# mother.net
KiCad netlist of a schematic drawn in EAGLE
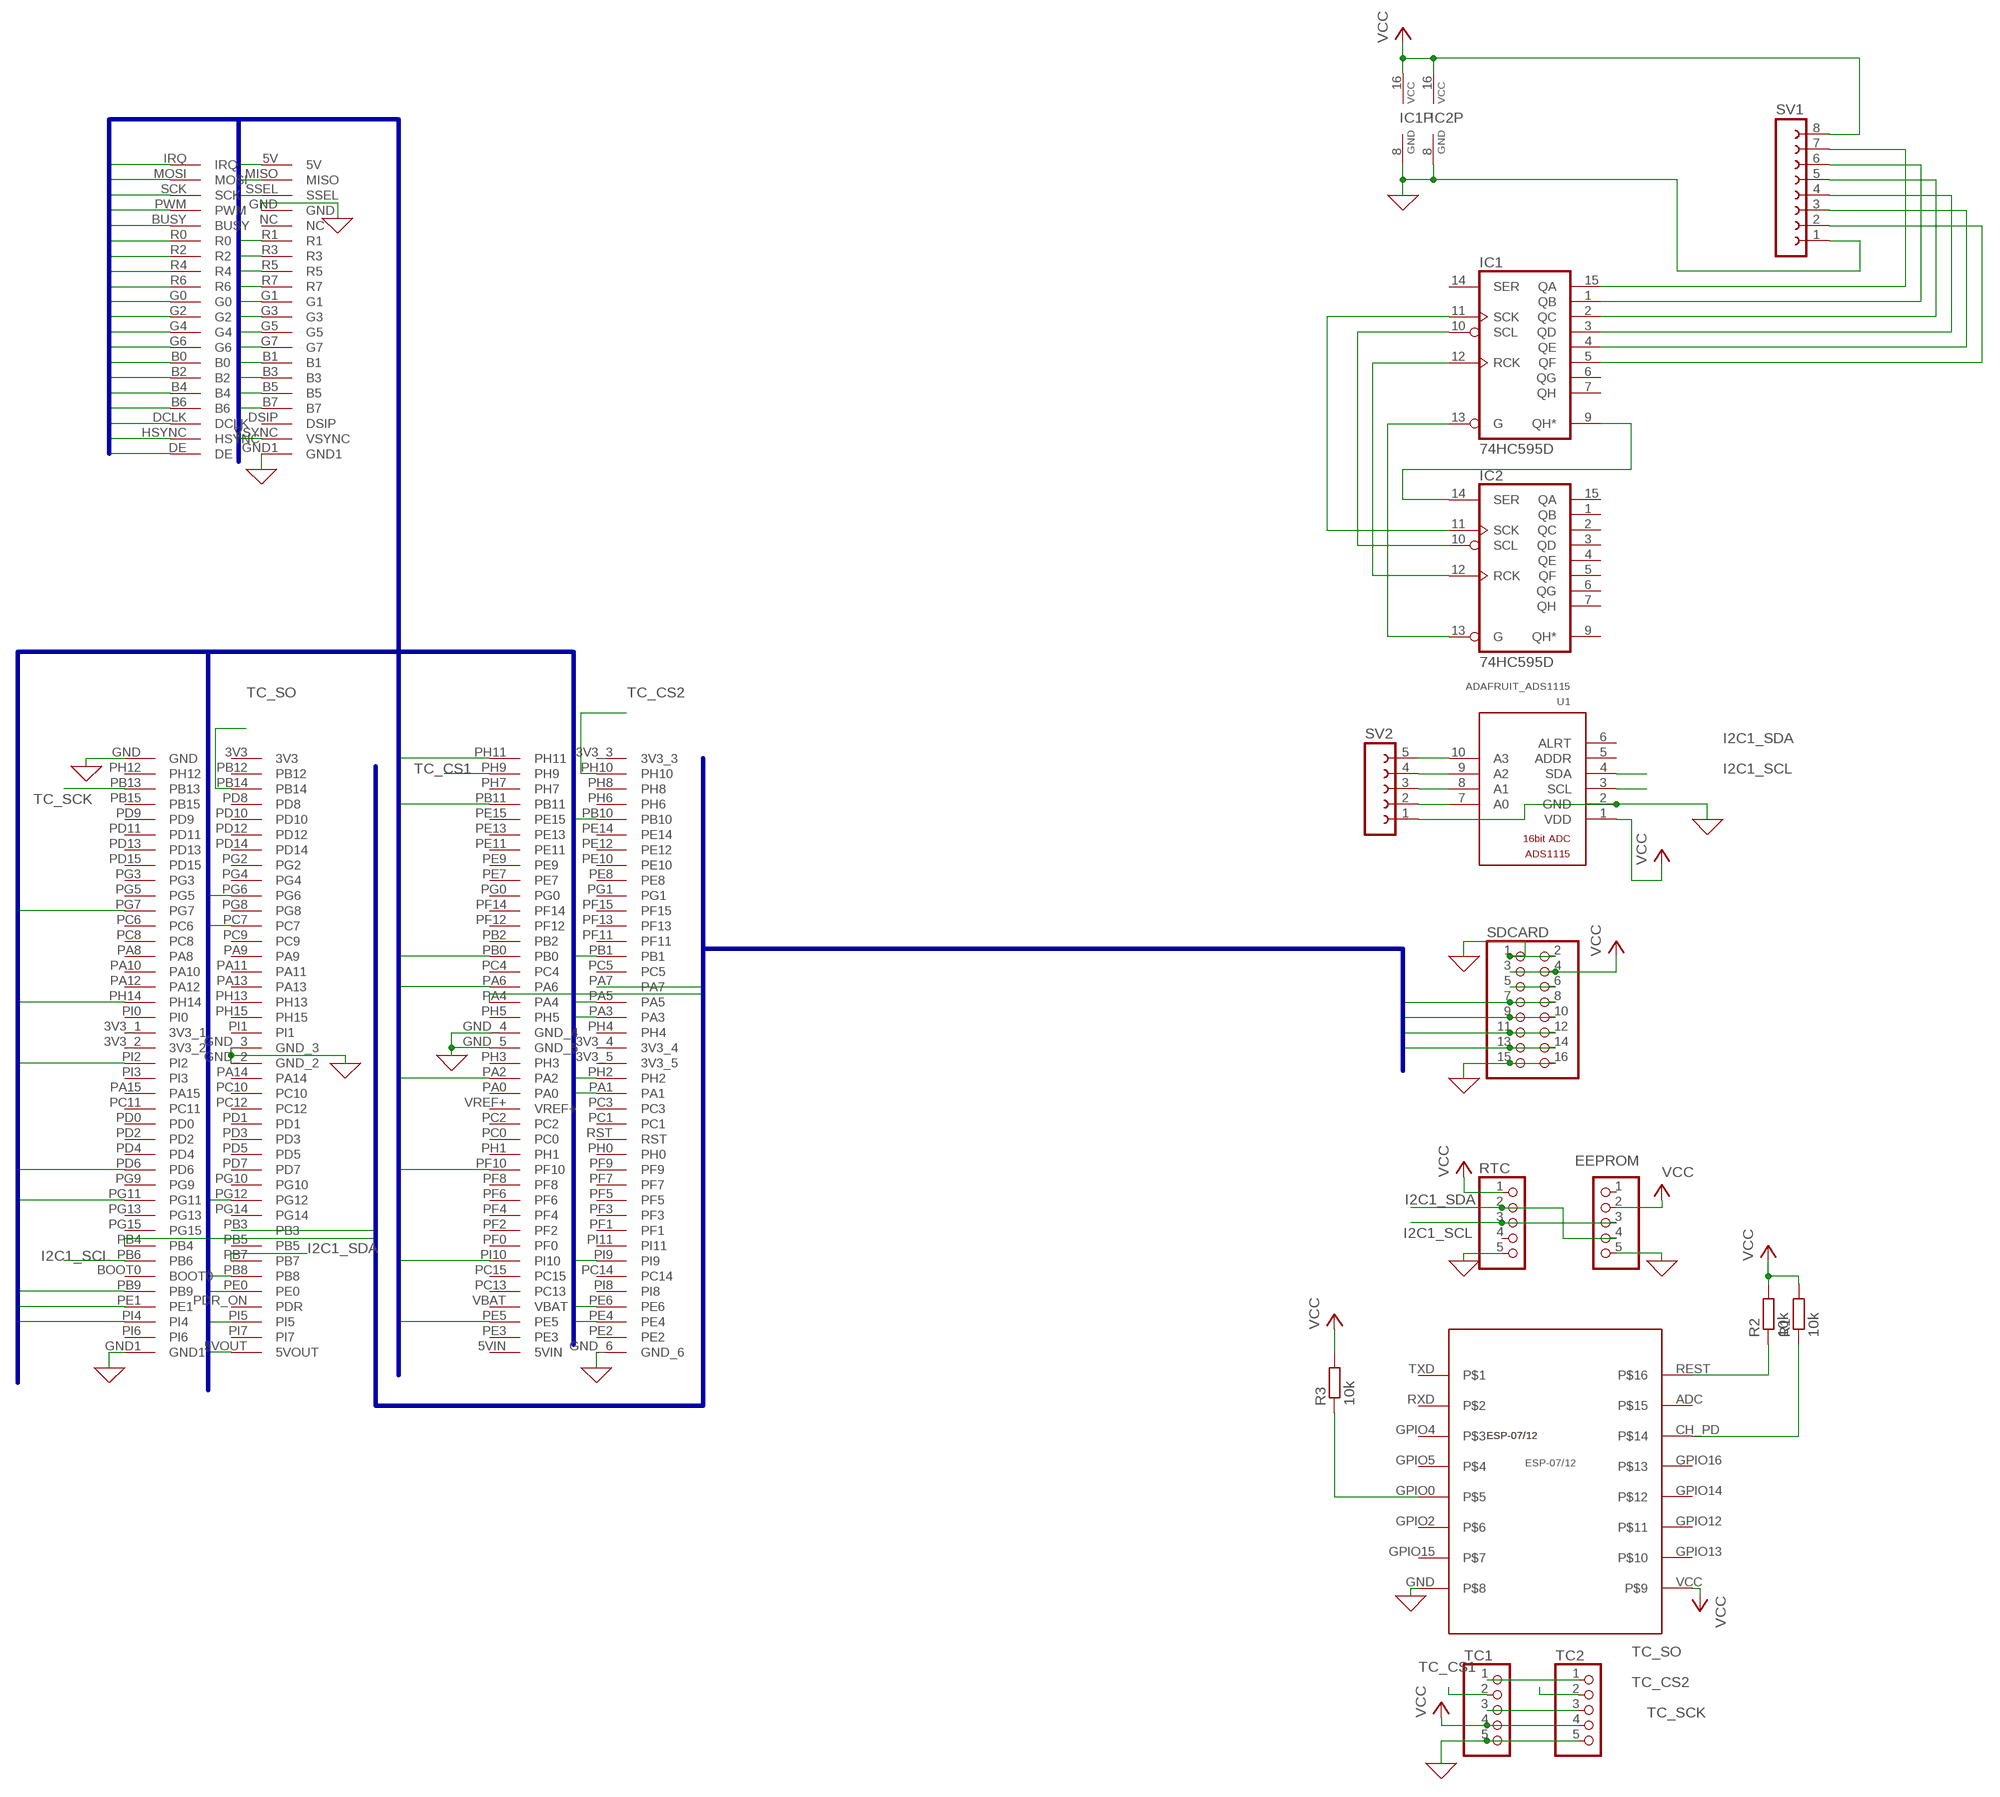
[diagram p0: schematic, sheet 1]

(export (version "E")
  (design (tool "Eeschema 10.0.6"))
  (components
    (comp (ref "EEPROM")
      (value "PINHD-1X5")
      (footprint "eagle-import:1X05")
      (libsource (lib "eagle-import") (part "PINHD-1X5"))
    )
    (comp (ref "IC1")
      (value "74HC595D")
      (footprint "eagle-import:SO16")
      (libsource (lib "eagle-import") (part "74595DHC"))
    )
    (comp (ref "IC2")
      (value "74HC595D")
      (footprint "eagle-import:SO16")
      (libsource (lib "eagle-import") (part "74595DHC"))
    )
    (comp (ref "R1")
      (value "10k")
      (footprint "eagle-import:R1206")
      (libsource (lib "eagle-import") (part "R-EU_R1206"))
    )
    (comp (ref "R2")
      (value "10k")
      (footprint "eagle-import:R1206")
      (libsource (lib "eagle-import") (part "R-EU_R1206"))
    )
    (comp (ref "R3")
      (value "10k")
      (footprint "eagle-import:R1206")
      (libsource (lib "eagle-import") (part "R-EU_R1206"))
    )
    (comp (ref "RTC")
      (value "PINHD-1X5")
      (footprint "eagle-import:1X05")
      (libsource (lib "eagle-import") (part "PINHD-1X5"))
    )
    (comp (ref "SDCARD")
      (value "PINHD-2X8")
      (footprint "eagle-import:2X08")
      (libsource (lib "eagle-import") (part "PINHD-2X8"))
    )
    (comp (ref "SV1")
      (value "FE08-1")
      (footprint "eagle-import:FE08")
      (libsource (lib "eagle-import") (part "FE08-1"))
    )
    (comp (ref "SV2")
      (value "FE05-1")
      (footprint "eagle-import:FE05-1")
      (libsource (lib "eagle-import") (part "FE05-1"))
    )
    (comp (ref "TC1")
      (value "PINHD-1X5")
      (footprint "eagle-import:1X05")
      (libsource (lib "eagle-import") (part "PINHD-1X5"))
    )
    (comp (ref "TC2")
      (value "PINHD-1X5")
      (footprint "eagle-import:1X05")
      (libsource (lib "eagle-import") (part "PINHD-1X5"))
    )
    (comp (ref "U$1")
      (value "LCDTFT")
      (footprint "eagle-import:4.3LCDTFT")
      (libsource (lib "eagle-import") (part "LCDTFT"))
    )
    (comp (ref "U$2")
      (value "HEADER2X40_2MM")
      (footprint "eagle-import:HEADER")
      (libsource (lib "eagle-import") (part "HEADER2X40_2MM"))
    )
    (comp (ref "U$3")
      (value "ESP-07/12")
      (footprint "eagle-import:ESP-07_12")
      (libsource (lib "eagle-import") (part "ESP-07/12"))
    )
    (comp (ref "U1")
      (value "ADAFRUIT_ADS1115")
      (footprint "eagle-import:ADAFRUIT_ADS1115_16BIT_I2C_ADC")
      (libsource (lib "eagle-import") (part "ADAFRUIT_ADS1115"))
    )
  )
  (nets
    (net (code "1") (name "/5V") (class "Default")
      (node (ref "U$1") (pin "5V") (pinfunction "5V_5V") (pintype "bidirectional"))
      (node (ref "U$2") (pin "5VOUT") (pinfunction "5VOUT_5VOUT") (pintype "bidirectional"))
    )
    (net (code "2") (name "/B0") (class "Default")
      (node (ref "U$1") (pin "B0") (pinfunction "B0_B0") (pintype "bidirectional"))
      (node (ref "U$2") (pin "PE4") (pinfunction "PE4_PE4") (pintype "bidirectional"))
    )
    (net (code "3") (name "/B1") (class "Default")
      (node (ref "U$1") (pin "B1") (pinfunction "B1_B1") (pintype "bidirectional"))
      (node (ref "U$2") (pin "PG12") (pinfunction "PG12_PG12") (pintype "bidirectional"))
    )
    (net (code "4") (name "/B2") (class "Default")
      (node (ref "U$1") (pin "B2") (pinfunction "B2_B2") (pintype "bidirectional"))
      (node (ref "U$2") (pin "PD6") (pinfunction "PD6_PD6") (pintype "bidirectional"))
    )
    (net (code "5") (name "/B3") (class "Default")
      (node (ref "U$1") (pin "B3") (pinfunction "B3_B3") (pintype "bidirectional"))
      (node (ref "U$2") (pin "PG11") (pinfunction "PG11_PG11") (pintype "bidirectional"))
    )
    (net (code "6") (name "/B4") (class "Default")
      (node (ref "U$1") (pin "B4") (pinfunction "B4_B4") (pintype "bidirectional"))
      (node (ref "U$2") (pin "PI4") (pinfunction "PI4_PI4") (pintype "bidirectional"))
    )
    (net (code "7") (name "/B5") (class "Default")
      (node (ref "U$1") (pin "B5") (pinfunction "B5_B5") (pintype "bidirectional"))
      (node (ref "U$2") (pin "PA3") (pinfunction "PA3_PA3") (pintype "bidirectional"))
    )
    (net (code "8") (name "/B6") (class "Default")
      (node (ref "U$1") (pin "B6") (pinfunction "B6_B6") (pintype "bidirectional"))
      (node (ref "U$2") (pin "PB8") (pinfunction "PB8_PB8") (pintype "bidirectional"))
    )
    (net (code "9") (name "/B7") (class "Default")
      (node (ref "U$1") (pin "B7") (pinfunction "B7_B7") (pintype "bidirectional"))
      (node (ref "U$2") (pin "PB9") (pinfunction "PB9_PB9") (pintype "bidirectional"))
    )
    (net (code "10") (name "/BUSY") (class "Default")
      (node (ref "U$1") (pin "BUSY") (pinfunction "BUSY_BUSY") (pintype "bidirectional"))
      (node (ref "U$2") (pin "PE0") (pinfunction "PE0_PE0") (pintype "bidirectional"))
    )
    (net (code "11") (name "/CLK") (class "Default")
      (node (ref "SDCARD") (pin "11") (pinfunction "11_11") (pintype "passive"))
      (node (ref "SDCARD") (pin "12") (pinfunction "12_12") (pintype "passive"))
      (node (ref "U$2") (pin "PB3") (pinfunction "PB3_PB3") (pintype "bidirectional"))
    )
    (net (code "12") (name "/CLK_LTDC") (class "Default")
      (node (ref "U$1") (pin "DCLK") (pinfunction "DCLK_DCLK") (pintype "bidirectional"))
      (node (ref "U$2") (pin "PG7") (pinfunction "PG7_PG7") (pintype "bidirectional"))
    )
    (net (code "13") (name "/CS") (class "Default")
      (node (ref "SDCARD") (pin "7") (pinfunction "7_7") (pintype "passive"))
      (node (ref "SDCARD") (pin "8") (pinfunction "8_8") (pintype "passive"))
      (node (ref "U$2") (pin "PA4") (pinfunction "PA4_PA4") (pintype "bidirectional"))
    )
    (net (code "14") (name "/DE") (class "Default")
      (node (ref "U$1") (pin "DE") (pinfunction "DE_DE") (pintype "bidirectional"))
      (node (ref "U$2") (pin "PF10") (pinfunction "PF10_PF10") (pintype "bidirectional"))
    )
    (net (code "15") (name "/G0") (class "Default")
      (node (ref "U$1") (pin "G0") (pinfunction "G0_G0") (pintype "bidirectional"))
      (node (ref "U$2") (pin "PE5") (pinfunction "PE5_PE5") (pintype "bidirectional"))
    )
    (net (code "16") (name "/G1") (class "Default")
      (node (ref "U$1") (pin "G1") (pinfunction "G1_G1") (pintype "bidirectional"))
      (node (ref "U$2") (pin "PE6") (pinfunction "PE6_PE6") (pintype "bidirectional"))
    )
    (net (code "17") (name "/G2") (class "Default")
      (node (ref "U$1") (pin "G2") (pinfunction "G2_G2") (pintype "bidirectional"))
      (node (ref "U$2") (pin "PA6") (pinfunction "PA6_PA6") (pintype "bidirectional"))
    )
    (net (code "18") (name "/G3") (class "Default")
      (node (ref "U$1") (pin "G3") (pinfunction "G3_G3") (pintype "bidirectional"))
      (node (ref "U$2") (pin "PH14") (pinfunction "PH14_PH14") (pintype "bidirectional"))
    )
    (net (code "19") (name "/G4") (class "Default")
      (node (ref "U$1") (pin "G4") (pinfunction "G4_G4") (pintype "bidirectional"))
      (node (ref "U$2") (pin "PB10") (pinfunction "PB10_PB10") (pintype "bidirectional"))
    )
    (net (code "20") (name "/G5") (class "Default")
      (node (ref "U$1") (pin "G5") (pinfunction "G5_G5") (pintype "bidirectional"))
      (node (ref "U$2") (pin "PB11") (pinfunction "PB11_PB11") (pintype "bidirectional"))
    )
    (net (code "21") (name "/G6") (class "Default")
      (node (ref "U$1") (pin "G6") (pinfunction "G6_G6") (pintype "bidirectional"))
      (node (ref "U$2") (pin "PC7") (pinfunction "PC7_PC7") (pintype "bidirectional"))
    )
    (net (code "22") (name "/G7") (class "Default")
      (node (ref "U$1") (pin "G7") (pinfunction "G7_G7") (pintype "bidirectional"))
      (node (ref "U$2") (pin "PI2") (pinfunction "PI2_PI2") (pintype "bidirectional"))
    )
    (net (code "23") (name "/HSYNC") (class "Default")
      (node (ref "U$1") (pin "HSYNC") (pinfunction "HSYNC_HSYNC") (pintype "bidirectional"))
      (node (ref "U$2") (pin "PI10") (pinfunction "PI10_PI10") (pintype "bidirectional"))
    )
    (net (code "24") (name "/I2C1_SCL") (class "Default")
      (node (ref "EEPROM") (pin "3") (pinfunction "3_3") (pintype "passive"))
      (node (ref "RTC") (pin "3") (pinfunction "3_3") (pintype "passive"))
      (node (ref "U$2") (pin "PB6") (pinfunction "PB6_PB6") (pintype "bidirectional"))
      (node (ref "U1") (pin "3") (pinfunction "SCL_3") (pintype "bidirectional"))
    )
    (net (code "25") (name "/I2C1_SDA") (class "Default")
      (node (ref "EEPROM") (pin "4") (pinfunction "4_4") (pintype "passive"))
      (node (ref "RTC") (pin "2") (pinfunction "2_2") (pintype "passive"))
      (node (ref "U$2") (pin "PB7") (pinfunction "PB7_PB7") (pintype "bidirectional"))
      (node (ref "U1") (pin "4") (pinfunction "SDA_4") (pintype "bidirectional"))
    )
    (net (code "26") (name "/IRQ") (class "Default")
      (node (ref "U$1") (pin "IRQ") (pinfunction "IRQ_IRQ") (pintype "bidirectional"))
      (node (ref "U$2") (pin "PE1") (pinfunction "PE1_PE1") (pintype "bidirectional"))
    )
    (net (code "27") (name "/MISO") (class "Default")
      (node (ref "SDCARD") (pin "13") (pinfunction "13_13") (pintype "passive"))
      (node (ref "SDCARD") (pin "14") (pinfunction "14_14") (pintype "passive"))
      (node (ref "U$2") (pin "PB4") (pinfunction "PB4_PB4") (pintype "bidirectional"))
    )
    (net (code "28") (name "/MOSI") (class "Default")
      (node (ref "SDCARD") (pin "10") (pinfunction "10_10") (pintype "passive"))
      (node (ref "SDCARD") (pin "9") (pinfunction "9_9") (pintype "passive"))
      (node (ref "U$2") (pin "PA7") (pinfunction "PA7_PA7") (pintype "bidirectional"))
    )
    (net (code "29") (name "/PWM") (class "Default")
      (node (ref "U$1") (pin "PWM") (pinfunction "PWM_PWM") (pintype "bidirectional"))
      (node (ref "U$2") (pin "PI5") (pinfunction "PI5_PI5") (pintype "bidirectional"))
    )
    (net (code "30") (name "/R0") (class "Default")
      (node (ref "U$1") (pin "R0") (pinfunction "R0_R0") (pintype "bidirectional"))
      (node (ref "U$2") (pin "PH2") (pinfunction "PH2_PH2") (pintype "bidirectional"))
    )
    (net (code "31") (name "/R1") (class "Default")
      (node (ref "U$1") (pin "R1") (pinfunction "R1_R1") (pintype "bidirectional"))
      (node (ref "U$2") (pin "PA2") (pinfunction "PA2_PA2") (pintype "bidirectional"))
    )
    (net (code "32") (name "/R2") (class "Default")
      (node (ref "U$1") (pin "R2") (pinfunction "R2_R2") (pintype "bidirectional"))
      (node (ref "U$2") (pin "PA1") (pinfunction "PA1_PA1") (pintype "bidirectional"))
    )
    (net (code "33") (name "/R3") (class "Default")
      (node (ref "U$1") (pin "R3") (pinfunction "R3_R3") (pintype "bidirectional"))
      (node (ref "U$2") (pin "PB0") (pinfunction "PB0_PB0") (pintype "bidirectional"))
    )
    (net (code "34") (name "/R4") (class "Default")
      (node (ref "U$1") (pin "R4") (pinfunction "R4_R4") (pintype "bidirectional"))
      (node (ref "U$2") (pin "PA5") (pinfunction "PA5_PA5") (pintype "bidirectional"))
    )
    (net (code "35") (name "/R5") (class "Default")
      (node (ref "U$1") (pin "R5") (pinfunction "R5_R5") (pintype "bidirectional"))
      (node (ref "U$2") (pin "PH11") (pinfunction "PH11_PH11") (pintype "bidirectional"))
    )
    (net (code "36") (name "/R6") (class "Default")
      (node (ref "U$1") (pin "R6") (pinfunction "R6_R6") (pintype "bidirectional"))
      (node (ref "U$2") (pin "PB1") (pinfunction "PB1_PB1") (pintype "bidirectional"))
    )
    (net (code "37") (name "/R7") (class "Default")
      (node (ref "U$1") (pin "R7") (pinfunction "R7_R7") (pintype "bidirectional"))
      (node (ref "U$2") (pin "PG6") (pinfunction "PG6_PG6") (pintype "bidirectional"))
    )
    (net (code "38") (name "/TC_CS1") (class "Default")
      (node (ref "TC1") (pin "2") (pinfunction "2_2") (pintype "passive"))
      (node (ref "U$2") (pin "PH9") (pinfunction "PH9_PH9") (pintype "bidirectional"))
    )
    (net (code "39") (name "/TC_CS2") (class "Default")
      (node (ref "TC2") (pin "2") (pinfunction "2_2") (pintype "passive"))
      (node (ref "U$2") (pin "PH10") (pinfunction "PH10_PH10") (pintype "bidirectional"))
    )
    (net (code "40") (name "/TC_SCK") (class "Default")
      (node (ref "TC1") (pin "3") (pinfunction "3_3") (pintype "passive"))
      (node (ref "TC2") (pin "3") (pinfunction "3_3") (pintype "passive"))
      (node (ref "U$2") (pin "PB13") (pinfunction "PB13_PB13") (pintype "bidirectional"))
    )
    (net (code "41") (name "/TC_SO") (class "Default")
      (node (ref "TC1") (pin "1") (pinfunction "1_1") (pintype "passive"))
      (node (ref "TC2") (pin "1") (pinfunction "1_1") (pintype "passive"))
      (node (ref "U$2") (pin "PB14") (pinfunction "PB14_PB14") (pintype "bidirectional"))
    )
    (net (code "42") (name "/VSYNC") (class "Default")
      (node (ref "U$1") (pin "VSYNC") (pinfunction "VSYNC_VSYNC") (pintype "bidirectional"))
      (node (ref "U$2") (pin "PI9") (pinfunction "PI9_PI9") (pintype "bidirectional"))
    )
    (net (code "43") (name "GND") (class "Default")
      (node (ref "EEPROM") (pin "5") (pinfunction "5_5") (pintype "passive"))
      (node (ref "IC1") (pin "8") (pinfunction "GND_8") (pintype "power_in"))
      (node (ref "IC2") (pin "8") (pinfunction "GND_8") (pintype "power_in"))
      (node (ref "RTC") (pin "5") (pinfunction "5_5") (pintype "passive"))
      (node (ref "SDCARD") (pin "1") (pinfunction "1_1") (pintype "passive"))
      (node (ref "SDCARD") (pin "15") (pinfunction "15_15") (pintype "passive"))
      (node (ref "SDCARD") (pin "16") (pinfunction "16_16") (pintype "passive"))
      (node (ref "SDCARD") (pin "2") (pinfunction "2_2") (pintype "passive"))
      (node (ref "SV1") (pin "1") (pinfunction "1_1") (pintype "passive"))
      (node (ref "SV2") (pin "1") (pinfunction "1_1") (pintype "passive"))
      (node (ref "TC1") (pin "5") (pinfunction "5_5") (pintype "passive"))
      (node (ref "TC2") (pin "5") (pinfunction "5_5") (pintype "passive"))
      (node (ref "U$1") (pin "GND") (pinfunction "GND_GND") (pintype "bidirectional"))
      (node (ref "U$1") (pin "GND1") (pinfunction "GND1_GND1") (pintype "bidirectional"))
      (node (ref "U$2") (pin "GND") (pinfunction "GND_GND") (pintype "bidirectional"))
      (node (ref "U$2") (pin "GND1") (pinfunction "GND1_GND1") (pintype "bidirectional"))
      (node (ref "U$2") (pin "GND_2") (pinfunction "GND_2_GND_2") (pintype "bidirectional"))
      (node (ref "U$2") (pin "GND_3") (pinfunction "GND_3_GND_3") (pintype "bidirectional"))
      (node (ref "U$2") (pin "GND_4") (pinfunction "GND_4_GND_4") (pintype "bidirectional"))
      (node (ref "U$2") (pin "GND_5") (pinfunction "GND_5_GND_5") (pintype "bidirectional"))
      (node (ref "U$2") (pin "GND_6") (pinfunction "GND_6_GND_6") (pintype "bidirectional"))
      (node (ref "U$3") (pin "GND") (pinfunction "P$8_GND") (pintype "bidirectional"))
      (node (ref "U1") (pin "2") (pinfunction "GND_2") (pintype "bidirectional"))
    )
    (net (code "44") (name "Net-(IC1A-G)") (class "Default")
      (node (ref "IC1") (pin "13") (pinfunction "G_13") (pintype "input"))
      (node (ref "IC2") (pin "13") (pinfunction "G_13") (pintype "input"))
    )
    (net (code "45") (name "Net-(IC1A-QA)") (class "Default")
      (node (ref "IC1") (pin "15") (pinfunction "QA_15") (pintype "tri_state"))
      (node (ref "SV1") (pin "7") (pinfunction "7_7") (pintype "passive"))
    )
    (net (code "46") (name "Net-(IC1A-QB)") (class "Default")
      (node (ref "IC1") (pin "1") (pinfunction "QB_1") (pintype "tri_state"))
      (node (ref "SV1") (pin "6") (pinfunction "6_6") (pintype "passive"))
    )
    (net (code "47") (name "Net-(IC1A-QC)") (class "Default")
      (node (ref "IC1") (pin "2") (pinfunction "QC_2") (pintype "tri_state"))
      (node (ref "SV1") (pin "5") (pinfunction "5_5") (pintype "passive"))
    )
    (net (code "48") (name "Net-(IC1A-QD)") (class "Default")
      (node (ref "IC1") (pin "3") (pinfunction "QD_3") (pintype "tri_state"))
      (node (ref "SV1") (pin "4") (pinfunction "4_4") (pintype "passive"))
    )
    (net (code "49") (name "Net-(IC1A-QE)") (class "Default")
      (node (ref "IC1") (pin "4") (pinfunction "QE_4") (pintype "tri_state"))
      (node (ref "SV1") (pin "3") (pinfunction "3_3") (pintype "passive"))
    )
    (net (code "50") (name "Net-(IC1A-QF)") (class "Default")
      (node (ref "IC1") (pin "5") (pinfunction "QF_5") (pintype "tri_state"))
      (node (ref "SV1") (pin "2") (pinfunction "2_2") (pintype "passive"))
    )
    (net (code "51") (name "Net-(IC1A-QH*)") (class "Default")
      (node (ref "IC1") (pin "9") (pinfunction "QH*_9") (pintype "tri_state"))
      (node (ref "IC2") (pin "14") (pinfunction "SER_14") (pintype "input"))
    )
    (net (code "52") (name "Net-(IC1A-RCK)") (class "Default")
      (node (ref "IC1") (pin "12") (pinfunction "RCK_12") (pintype "input"))
      (node (ref "IC2") (pin "12") (pinfunction "RCK_12") (pintype "input"))
    )
    (net (code "53") (name "Net-(IC1A-SCK)") (class "Default")
      (node (ref "IC1") (pin "11") (pinfunction "SCK_11") (pintype "input"))
      (node (ref "IC2") (pin "11") (pinfunction "SCK_11") (pintype "input"))
    )
    (net (code "54") (name "Net-(IC1A-SCL)") (class "Default")
      (node (ref "IC1") (pin "10") (pinfunction "SCL_10") (pintype "input"))
      (node (ref "IC2") (pin "10") (pinfunction "SCL_10") (pintype "input"))
    )
    (net (code "55") (name "Net-(SDCARD-Pad5)") (class "Default")
      (node (ref "SDCARD") (pin "5") (pinfunction "5_5") (pintype "passive"))
      (node (ref "SDCARD") (pin "6") (pinfunction "6_6") (pintype "passive"))
    )
    (net (code "56") (name "Net-(U$3-P$5)") (class "Default")
      (node (ref "R3") (pin "1") (pinfunction "1_1") (pintype "passive"))
      (node (ref "U$3") (pin "GPIO0") (pinfunction "P$5_GPIO0") (pintype "bidirectional"))
    )
    (net (code "57") (name "Net-(U$3-P$14)") (class "Default")
      (node (ref "R1") (pin "1") (pinfunction "1_1") (pintype "passive"))
      (node (ref "U$3") (pin "CH_PD") (pinfunction "P$14_CH_PD") (pintype "bidirectional"))
    )
    (net (code "58") (name "Net-(U$3-P$16)") (class "Default")
      (node (ref "R2") (pin "1") (pinfunction "1_1") (pintype "passive"))
      (node (ref "U$3") (pin "REST") (pinfunction "P$16_REST") (pintype "bidirectional"))
    )
    (net (code "59") (name "Net-(U1-A0)") (class "Default")
      (node (ref "SV2") (pin "2") (pinfunction "2_2") (pintype "passive"))
      (node (ref "U1") (pin "7") (pinfunction "A0_7") (pintype "bidirectional"))
    )
    (net (code "60") (name "Net-(U1-A1)") (class "Default")
      (node (ref "SV2") (pin "3") (pinfunction "3_3") (pintype "passive"))
      (node (ref "U1") (pin "8") (pinfunction "A1_8") (pintype "bidirectional"))
    )
    (net (code "61") (name "Net-(U1-A2)") (class "Default")
      (node (ref "SV2") (pin "4") (pinfunction "4_4") (pintype "passive"))
      (node (ref "U1") (pin "9") (pinfunction "A2_9") (pintype "bidirectional"))
    )
    (net (code "62") (name "Net-(U1-A3)") (class "Default")
      (node (ref "SV2") (pin "5") (pinfunction "5_5") (pintype "passive"))
      (node (ref "U1") (pin "10") (pinfunction "A3_10") (pintype "bidirectional"))
    )
    (net (code "63") (name "VCC") (class "Default")
      (node (ref "EEPROM") (pin "2") (pinfunction "2_2") (pintype "passive"))
      (node (ref "IC1") (pin "16") (pinfunction "VCC_16") (pintype "power_in"))
      (node (ref "IC2") (pin "16") (pinfunction "VCC_16") (pintype "power_in"))
      (node (ref "R1") (pin "2") (pinfunction "2_2") (pintype "passive"))
      (node (ref "R2") (pin "2") (pinfunction "2_2") (pintype "passive"))
      (node (ref "R3") (pin "2") (pinfunction "2_2") (pintype "passive"))
      (node (ref "RTC") (pin "1") (pinfunction "1_1") (pintype "passive"))
      (node (ref "SDCARD") (pin "3") (pinfunction "3_3") (pintype "passive"))
      (node (ref "SDCARD") (pin "4") (pinfunction "4_4") (pintype "passive"))
      (node (ref "SV1") (pin "8") (pinfunction "8_8") (pintype "passive"))
      (node (ref "TC1") (pin "4") (pinfunction "4_4") (pintype "passive"))
      (node (ref "TC2") (pin "4") (pinfunction "4_4") (pintype "passive"))
      (node (ref "U$3") (pin "VCC") (pinfunction "P$9_VCC") (pintype "bidirectional"))
      (node (ref "U1") (pin "1") (pinfunction "VDD_1") (pintype "bidirectional"))
    )
    (net (code "64") (name "unconnected-(EEPROM-Pad1)") (class "Default")
      (node (ref "EEPROM") (pin "1") (pinfunction "1_1") (pintype "passive"))
    )
    (net (code "65") (name "unconnected-(IC1A-QG-Pad6)") (class "Default")
      (node (ref "IC1") (pin "6") (pinfunction "QG_6") (pintype "tri_state"))
    )
    (net (code "66") (name "unconnected-(IC1A-QH-Pad7)") (class "Default")
      (node (ref "IC1") (pin "7") (pinfunction "QH_7") (pintype "tri_state"))
    )
    (net (code "67") (name "unconnected-(IC1A-SER-Pad14)") (class "Default")
      (node (ref "IC1") (pin "14") (pinfunction "SER_14") (pintype "input"))
    )
    (net (code "68") (name "unconnected-(IC2A-QA-Pad15)") (class "Default")
      (node (ref "IC2") (pin "15") (pinfunction "QA_15") (pintype "tri_state"))
    )
    (net (code "69") (name "unconnected-(IC2A-QB-Pad1)") (class "Default")
      (node (ref "IC2") (pin "1") (pinfunction "QB_1") (pintype "tri_state"))
    )
    (net (code "70") (name "unconnected-(IC2A-QC-Pad2)") (class "Default")
      (node (ref "IC2") (pin "2") (pinfunction "QC_2") (pintype "tri_state"))
    )
    (net (code "71") (name "unconnected-(IC2A-QD-Pad3)") (class "Default")
      (node (ref "IC2") (pin "3") (pinfunction "QD_3") (pintype "tri_state"))
    )
    (net (code "72") (name "unconnected-(IC2A-QE-Pad4)") (class "Default")
      (node (ref "IC2") (pin "4") (pinfunction "QE_4") (pintype "tri_state"))
    )
    (net (code "73") (name "unconnected-(IC2A-QF-Pad5)") (class "Default")
      (node (ref "IC2") (pin "5") (pinfunction "QF_5") (pintype "tri_state"))
    )
    (net (code "74") (name "unconnected-(IC2A-QG-Pad6)") (class "Default")
      (node (ref "IC2") (pin "6") (pinfunction "QG_6") (pintype "tri_state"))
    )
    (net (code "75") (name "unconnected-(IC2A-QH*-Pad9)") (class "Default")
      (node (ref "IC2") (pin "9") (pinfunction "QH*_9") (pintype "tri_state"))
    )
    (net (code "76") (name "unconnected-(IC2A-QH-Pad7)") (class "Default")
      (node (ref "IC2") (pin "7") (pinfunction "QH_7") (pintype "tri_state"))
    )
    (net (code "77") (name "unconnected-(RTC-Pad4)") (class "Default")
      (node (ref "RTC") (pin "4") (pinfunction "4_4") (pintype "passive"))
    )
    (net (code "78") (name "unconnected-(U$1-PadDSIP)") (class "Default")
      (node (ref "U$1") (pin "DSIP") (pinfunction "DSIP_DSIP") (pintype "bidirectional"))
    )
    (net (code "79") (name "unconnected-(U$1-PadMISO)") (class "Default")
      (node (ref "U$1") (pin "MISO") (pinfunction "MISO_MISO") (pintype "bidirectional"))
    )
    (net (code "80") (name "unconnected-(U$1-PadMOSI)") (class "Default")
      (node (ref "U$1") (pin "MOSI") (pinfunction "MOSI_MOSI") (pintype "bidirectional"))
    )
    (net (code "81") (name "unconnected-(U$1-PadNC)") (class "Default")
      (node (ref "U$1") (pin "NC") (pinfunction "NC_NC") (pintype "bidirectional"))
    )
    (net (code "82") (name "unconnected-(U$1-PadSCK)") (class "Default")
      (node (ref "U$1") (pin "SCK") (pinfunction "SCK_SCK") (pintype "bidirectional"))
    )
    (net (code "83") (name "unconnected-(U$1-PadSSEL)") (class "Default")
      (node (ref "U$1") (pin "SSEL") (pinfunction "SSEL_SSEL") (pintype "bidirectional"))
    )
    (net (code "84") (name "unconnected-(U$2-PDR-PadPDR_ON)") (class "Default")
      (node (ref "U$2") (pin "PDR_ON") (pinfunction "PDR_PDR_ON") (pintype "bidirectional"))
    )
    (net (code "85") (name "unconnected-(U$2-Pad3V3)") (class "Default")
      (node (ref "U$2") (pin "3V3") (pinfunction "3V3_3V3") (pintype "bidirectional"))
    )
    (net (code "86") (name "unconnected-(U$2-Pad3V3_1)") (class "Default")
      (node (ref "U$2") (pin "3V3_1") (pinfunction "3V3_1_3V3_1") (pintype "bidirectional"))
    )
    (net (code "87") (name "unconnected-(U$2-Pad3V3_2)") (class "Default")
      (node (ref "U$2") (pin "3V3_2") (pinfunction "3V3_2_3V3_2") (pintype "bidirectional"))
    )
    (net (code "88") (name "unconnected-(U$2-Pad3V3_3)") (class "Default")
      (node (ref "U$2") (pin "3V3_3") (pinfunction "3V3_3_3V3_3") (pintype "bidirectional"))
    )
    (net (code "89") (name "unconnected-(U$2-Pad3V3_4)") (class "Default")
      (node (ref "U$2") (pin "3V3_4") (pinfunction "3V3_4_3V3_4") (pintype "bidirectional"))
    )
    (net (code "90") (name "unconnected-(U$2-Pad3V3_5)") (class "Default")
      (node (ref "U$2") (pin "3V3_5") (pinfunction "3V3_5_3V3_5") (pintype "bidirectional"))
    )
    (net (code "91") (name "unconnected-(U$2-Pad5VIN)") (class "Default")
      (node (ref "U$2") (pin "5VIN") (pinfunction "5VIN_5VIN") (pintype "bidirectional"))
    )
    (net (code "92") (name "unconnected-(U$2-PadBOOT0)") (class "Default")
      (node (ref "U$2") (pin "BOOT0") (pinfunction "BOOT0_BOOT0") (pintype "bidirectional"))
    )
    (net (code "93") (name "unconnected-(U$2-PadPA0)") (class "Default")
      (node (ref "U$2") (pin "PA0") (pinfunction "PA0_PA0") (pintype "bidirectional"))
    )
    (net (code "94") (name "unconnected-(U$2-PadPA8)") (class "Default")
      (node (ref "U$2") (pin "PA8") (pinfunction "PA8_PA8") (pintype "bidirectional"))
    )
    (net (code "95") (name "unconnected-(U$2-PadPA9)") (class "Default")
      (node (ref "U$2") (pin "PA9") (pinfunction "PA9_PA9") (pintype "bidirectional"))
    )
    (net (code "96") (name "unconnected-(U$2-PadPA10)") (class "Default")
      (node (ref "U$2") (pin "PA10") (pinfunction "PA10_PA10") (pintype "bidirectional"))
    )
    (net (code "97") (name "unconnected-(U$2-PadPA11)") (class "Default")
      (node (ref "U$2") (pin "PA11") (pinfunction "PA11_PA11") (pintype "bidirectional"))
    )
    (net (code "98") (name "unconnected-(U$2-PadPA12)") (class "Default")
      (node (ref "U$2") (pin "PA12") (pinfunction "PA12_PA12") (pintype "bidirectional"))
    )
    (net (code "99") (name "unconnected-(U$2-PadPA13)") (class "Default")
      (node (ref "U$2") (pin "PA13") (pinfunction "PA13_PA13") (pintype "bidirectional"))
    )
    (net (code "100") (name "unconnected-(U$2-PadPA14)") (class "Default")
      (node (ref "U$2") (pin "PA14") (pinfunction "PA14_PA14") (pintype "bidirectional"))
    )
    (net (code "101") (name "unconnected-(U$2-PadPA15)") (class "Default")
      (node (ref "U$2") (pin "PA15") (pinfunction "PA15_PA15") (pintype "bidirectional"))
    )
    (net (code "102") (name "unconnected-(U$2-PadPB2)") (class "Default")
      (node (ref "U$2") (pin "PB2") (pinfunction "PB2_PB2") (pintype "bidirectional"))
    )
    (net (code "103") (name "unconnected-(U$2-PadPB5)") (class "Default")
      (node (ref "U$2") (pin "PB5") (pinfunction "PB5_PB5") (pintype "bidirectional"))
    )
    (net (code "104") (name "unconnected-(U$2-PadPB12)") (class "Default")
      (node (ref "U$2") (pin "PB12") (pinfunction "PB12_PB12") (pintype "bidirectional"))
    )
    (net (code "105") (name "unconnected-(U$2-PadPB15)") (class "Default")
      (node (ref "U$2") (pin "PB15") (pinfunction "PB15_PB15") (pintype "bidirectional"))
    )
    (net (code "106") (name "unconnected-(U$2-PadPC0)") (class "Default")
      (node (ref "U$2") (pin "PC0") (pinfunction "PC0_PC0") (pintype "bidirectional"))
    )
    (net (code "107") (name "unconnected-(U$2-PadPC1)") (class "Default")
      (node (ref "U$2") (pin "PC1") (pinfunction "PC1_PC1") (pintype "bidirectional"))
    )
    (net (code "108") (name "unconnected-(U$2-PadPC2)") (class "Default")
      (node (ref "U$2") (pin "PC2") (pinfunction "PC2_PC2") (pintype "bidirectional"))
    )
    (net (code "109") (name "unconnected-(U$2-PadPC3)") (class "Default")
      (node (ref "U$2") (pin "PC3") (pinfunction "PC3_PC3") (pintype "bidirectional"))
    )
    (net (code "110") (name "unconnected-(U$2-PadPC4)") (class "Default")
      (node (ref "U$2") (pin "PC4") (pinfunction "PC4_PC4") (pintype "bidirectional"))
    )
    (net (code "111") (name "unconnected-(U$2-PadPC5)") (class "Default")
      (node (ref "U$2") (pin "PC5") (pinfunction "PC5_PC5") (pintype "bidirectional"))
    )
    (net (code "112") (name "unconnected-(U$2-PadPC6)") (class "Default")
      (node (ref "U$2") (pin "PC6") (pinfunction "PC6_PC6") (pintype "bidirectional"))
    )
    (net (code "113") (name "unconnected-(U$2-PadPC8)") (class "Default")
      (node (ref "U$2") (pin "PC8") (pinfunction "PC8_PC8") (pintype "bidirectional"))
    )
    (net (code "114") (name "unconnected-(U$2-PadPC9)") (class "Default")
      (node (ref "U$2") (pin "PC9") (pinfunction "PC9_PC9") (pintype "bidirectional"))
    )
    (net (code "115") (name "unconnected-(U$2-PadPC10)") (class "Default")
      (node (ref "U$2") (pin "PC10") (pinfunction "PC10_PC10") (pintype "bidirectional"))
    )
    (net (code "116") (name "unconnected-(U$2-PadPC11)") (class "Default")
      (node (ref "U$2") (pin "PC11") (pinfunction "PC11_PC11") (pintype "bidirectional"))
    )
    (net (code "117") (name "unconnected-(U$2-PadPC12)") (class "Default")
      (node (ref "U$2") (pin "PC12") (pinfunction "PC12_PC12") (pintype "bidirectional"))
    )
    (net (code "118") (name "unconnected-(U$2-PadPC13)") (class "Default")
      (node (ref "U$2") (pin "PC13") (pinfunction "PC13_PC13") (pintype "bidirectional"))
    )
    (net (code "119") (name "unconnected-(U$2-PadPC14)") (class "Default")
      (node (ref "U$2") (pin "PC14") (pinfunction "PC14_PC14") (pintype "bidirectional"))
    )
    (net (code "120") (name "unconnected-(U$2-PadPC15)") (class "Default")
      (node (ref "U$2") (pin "PC15") (pinfunction "PC15_PC15") (pintype "bidirectional"))
    )
    (net (code "121") (name "unconnected-(U$2-PadPD0)") (class "Default")
      (node (ref "U$2") (pin "PD0") (pinfunction "PD0_PD0") (pintype "bidirectional"))
    )
    (net (code "122") (name "unconnected-(U$2-PadPD1)") (class "Default")
      (node (ref "U$2") (pin "PD1") (pinfunction "PD1_PD1") (pintype "bidirectional"))
    )
    (net (code "123") (name "unconnected-(U$2-PadPD2)") (class "Default")
      (node (ref "U$2") (pin "PD2") (pinfunction "PD2_PD2") (pintype "bidirectional"))
    )
    (net (code "124") (name "unconnected-(U$2-PadPD3)") (class "Default")
      (node (ref "U$2") (pin "PD3") (pinfunction "PD3_PD3") (pintype "bidirectional"))
    )
    (net (code "125") (name "unconnected-(U$2-PadPD4)") (class "Default")
      (node (ref "U$2") (pin "PD4") (pinfunction "PD4_PD4") (pintype "bidirectional"))
    )
    (net (code "126") (name "unconnected-(U$2-PadPD5)") (class "Default")
      (node (ref "U$2") (pin "PD5") (pinfunction "PD5_PD5") (pintype "bidirectional"))
    )
    (net (code "127") (name "unconnected-(U$2-PadPD7)") (class "Default")
      (node (ref "U$2") (pin "PD7") (pinfunction "PD7_PD7") (pintype "bidirectional"))
    )
    (net (code "128") (name "unconnected-(U$2-PadPD8)") (class "Default")
      (node (ref "U$2") (pin "PD8") (pinfunction "PD8_PD8") (pintype "bidirectional"))
    )
    (net (code "129") (name "unconnected-(U$2-PadPD9)") (class "Default")
      (node (ref "U$2") (pin "PD9") (pinfunction "PD9_PD9") (pintype "bidirectional"))
    )
    (net (code "130") (name "unconnected-(U$2-PadPD10)") (class "Default")
      (node (ref "U$2") (pin "PD10") (pinfunction "PD10_PD10") (pintype "bidirectional"))
    )
    (net (code "131") (name "unconnected-(U$2-PadPD11)") (class "Default")
      (node (ref "U$2") (pin "PD11") (pinfunction "PD11_PD11") (pintype "bidirectional"))
    )
    (net (code "132") (name "unconnected-(U$2-PadPD12)") (class "Default")
      (node (ref "U$2") (pin "PD12") (pinfunction "PD12_PD12") (pintype "bidirectional"))
    )
    (net (code "133") (name "unconnected-(U$2-PadPD13)") (class "Default")
      (node (ref "U$2") (pin "PD13") (pinfunction "PD13_PD13") (pintype "bidirectional"))
    )
    (net (code "134") (name "unconnected-(U$2-PadPD14)") (class "Default")
      (node (ref "U$2") (pin "PD14") (pinfunction "PD14_PD14") (pintype "bidirectional"))
    )
    (net (code "135") (name "unconnected-(U$2-PadPD15)") (class "Default")
      (node (ref "U$2") (pin "PD15") (pinfunction "PD15_PD15") (pintype "bidirectional"))
    )
    (net (code "136") (name "unconnected-(U$2-PadPE2)") (class "Default")
      (node (ref "U$2") (pin "PE2") (pinfunction "PE2_PE2") (pintype "bidirectional"))
    )
    (net (code "137") (name "unconnected-(U$2-PadPE3)") (class "Default")
      (node (ref "U$2") (pin "PE3") (pinfunction "PE3_PE3") (pintype "bidirectional"))
    )
    (net (code "138") (name "unconnected-(U$2-PadPE7)") (class "Default")
      (node (ref "U$2") (pin "PE7") (pinfunction "PE7_PE7") (pintype "bidirectional"))
    )
    (net (code "139") (name "unconnected-(U$2-PadPE8)") (class "Default")
      (node (ref "U$2") (pin "PE8") (pinfunction "PE8_PE8") (pintype "bidirectional"))
    )
    (net (code "140") (name "unconnected-(U$2-PadPE9)") (class "Default")
      (node (ref "U$2") (pin "PE9") (pinfunction "PE9_PE9") (pintype "bidirectional"))
    )
    (net (code "141") (name "unconnected-(U$2-PadPE10)") (class "Default")
      (node (ref "U$2") (pin "PE10") (pinfunction "PE10_PE10") (pintype "bidirectional"))
    )
    (net (code "142") (name "unconnected-(U$2-PadPE11)") (class "Default")
      (node (ref "U$2") (pin "PE11") (pinfunction "PE11_PE11") (pintype "bidirectional"))
    )
    (net (code "143") (name "unconnected-(U$2-PadPE12)") (class "Default")
      (node (ref "U$2") (pin "PE12") (pinfunction "PE12_PE12") (pintype "bidirectional"))
    )
    (net (code "144") (name "unconnected-(U$2-PadPE13)") (class "Default")
      (node (ref "U$2") (pin "PE13") (pinfunction "PE13_PE13") (pintype "bidirectional"))
    )
    (net (code "145") (name "unconnected-(U$2-PadPE14)") (class "Default")
      (node (ref "U$2") (pin "PE14") (pinfunction "PE14_PE14") (pintype "bidirectional"))
    )
    (net (code "146") (name "unconnected-(U$2-PadPE15)") (class "Default")
      (node (ref "U$2") (pin "PE15") (pinfunction "PE15_PE15") (pintype "bidirectional"))
    )
    (net (code "147") (name "unconnected-(U$2-PadPF0)") (class "Default")
      (node (ref "U$2") (pin "PF0") (pinfunction "PF0_PF0") (pintype "bidirectional"))
    )
    (net (code "148") (name "unconnected-(U$2-PadPF1)") (class "Default")
      (node (ref "U$2") (pin "PF1") (pinfunction "PF1_PF1") (pintype "bidirectional"))
    )
    (net (code "149") (name "unconnected-(U$2-PadPF2)") (class "Default")
      (node (ref "U$2") (pin "PF2") (pinfunction "PF2_PF2") (pintype "bidirectional"))
    )
    (net (code "150") (name "unconnected-(U$2-PadPF3)") (class "Default")
      (node (ref "U$2") (pin "PF3") (pinfunction "PF3_PF3") (pintype "bidirectional"))
    )
    (net (code "151") (name "unconnected-(U$2-PadPF4)") (class "Default")
      (node (ref "U$2") (pin "PF4") (pinfunction "PF4_PF4") (pintype "bidirectional"))
    )
    (net (code "152") (name "unconnected-(U$2-PadPF5)") (class "Default")
      (node (ref "U$2") (pin "PF5") (pinfunction "PF5_PF5") (pintype "bidirectional"))
    )
    (net (code "153") (name "unconnected-(U$2-PadPF6)") (class "Default")
      (node (ref "U$2") (pin "PF6") (pinfunction "PF6_PF6") (pintype "bidirectional"))
    )
    (net (code "154") (name "unconnected-(U$2-PadPF7)") (class "Default")
      (node (ref "U$2") (pin "PF7") (pinfunction "PF7_PF7") (pintype "bidirectional"))
    )
    (net (code "155") (name "unconnected-(U$2-PadPF8)") (class "Default")
      (node (ref "U$2") (pin "PF8") (pinfunction "PF8_PF8") (pintype "bidirectional"))
    )
    (net (code "156") (name "unconnected-(U$2-PadPF9)") (class "Default")
      (node (ref "U$2") (pin "PF9") (pinfunction "PF9_PF9") (pintype "bidirectional"))
    )
    (net (code "157") (name "unconnected-(U$2-PadPF11)") (class "Default")
      (node (ref "U$2") (pin "PF11") (pinfunction "PF11_PF11") (pintype "bidirectional"))
    )
    (net (code "158") (name "unconnected-(U$2-PadPF12)") (class "Default")
      (node (ref "U$2") (pin "PF12") (pinfunction "PF12_PF12") (pintype "bidirectional"))
    )
    (net (code "159") (name "unconnected-(U$2-PadPF13)") (class "Default")
      (node (ref "U$2") (pin "PF13") (pinfunction "PF13_PF13") (pintype "bidirectional"))
    )
    (net (code "160") (name "unconnected-(U$2-PadPF14)") (class "Default")
      (node (ref "U$2") (pin "PF14") (pinfunction "PF14_PF14") (pintype "bidirectional"))
    )
    (net (code "161") (name "unconnected-(U$2-PadPF15)") (class "Default")
      (node (ref "U$2") (pin "PF15") (pinfunction "PF15_PF15") (pintype "bidirectional"))
    )
    (net (code "162") (name "unconnected-(U$2-PadPG0)") (class "Default")
      (node (ref "U$2") (pin "PG0") (pinfunction "PG0_PG0") (pintype "bidirectional"))
    )
    (net (code "163") (name "unconnected-(U$2-PadPG1)") (class "Default")
      (node (ref "U$2") (pin "PG1") (pinfunction "PG1_PG1") (pintype "bidirectional"))
    )
    (net (code "164") (name "unconnected-(U$2-PadPG2)") (class "Default")
      (node (ref "U$2") (pin "PG2") (pinfunction "PG2_PG2") (pintype "bidirectional"))
    )
    (net (code "165") (name "unconnected-(U$2-PadPG3)") (class "Default")
      (node (ref "U$2") (pin "PG3") (pinfunction "PG3_PG3") (pintype "bidirectional"))
    )
    (net (code "166") (name "unconnected-(U$2-PadPG4)") (class "Default")
      (node (ref "U$2") (pin "PG4") (pinfunction "PG4_PG4") (pintype "bidirectional"))
    )
    (net (code "167") (name "unconnected-(U$2-PadPG5)") (class "Default")
      (node (ref "U$2") (pin "PG5") (pinfunction "PG5_PG5") (pintype "bidirectional"))
    )
    (net (code "168") (name "unconnected-(U$2-PadPG8)") (class "Default")
      (node (ref "U$2") (pin "PG8") (pinfunction "PG8_PG8") (pintype "bidirectional"))
    )
    (net (code "169") (name "unconnected-(U$2-PadPG9)") (class "Default")
      (node (ref "U$2") (pin "PG9") (pinfunction "PG9_PG9") (pintype "bidirectional"))
    )
    (net (code "170") (name "unconnected-(U$2-PadPG10)") (class "Default")
      (node (ref "U$2") (pin "PG10") (pinfunction "PG10_PG10") (pintype "bidirectional"))
    )
    (net (code "171") (name "unconnected-(U$2-PadPG13)") (class "Default")
      (node (ref "U$2") (pin "PG13") (pinfunction "PG13_PG13") (pintype "bidirectional"))
    )
    (net (code "172") (name "unconnected-(U$2-PadPG14)") (class "Default")
      (node (ref "U$2") (pin "PG14") (pinfunction "PG14_PG14") (pintype "bidirectional"))
    )
    (net (code "173") (name "unconnected-(U$2-PadPG15)") (class "Default")
      (node (ref "U$2") (pin "PG15") (pinfunction "PG15_PG15") (pintype "bidirectional"))
    )
    (net (code "174") (name "unconnected-(U$2-PadPH0)") (class "Default")
      (node (ref "U$2") (pin "PH0") (pinfunction "PH0_PH0") (pintype "bidirectional"))
    )
    (net (code "175") (name "unconnected-(U$2-PadPH1)") (class "Default")
      (node (ref "U$2") (pin "PH1") (pinfunction "PH1_PH1") (pintype "bidirectional"))
    )
    (net (code "176") (name "unconnected-(U$2-PadPH3)") (class "Default")
      (node (ref "U$2") (pin "PH3") (pinfunction "PH3_PH3") (pintype "bidirectional"))
    )
    (net (code "177") (name "unconnected-(U$2-PadPH4)") (class "Default")
      (node (ref "U$2") (pin "PH4") (pinfunction "PH4_PH4") (pintype "bidirectional"))
    )
    (net (code "178") (name "unconnected-(U$2-PadPH5)") (class "Default")
      (node (ref "U$2") (pin "PH5") (pinfunction "PH5_PH5") (pintype "bidirectional"))
    )
    (net (code "179") (name "unconnected-(U$2-PadPH6)") (class "Default")
      (node (ref "U$2") (pin "PH6") (pinfunction "PH6_PH6") (pintype "bidirectional"))
    )
    (net (code "180") (name "unconnected-(U$2-PadPH7)") (class "Default")
      (node (ref "U$2") (pin "PH7") (pinfunction "PH7_PH7") (pintype "bidirectional"))
    )
    (net (code "181") (name "unconnected-(U$2-PadPH8)") (class "Default")
      (node (ref "U$2") (pin "PH8") (pinfunction "PH8_PH8") (pintype "bidirectional"))
    )
    (net (code "182") (name "unconnected-(U$2-PadPH12)") (class "Default")
      (node (ref "U$2") (pin "PH12") (pinfunction "PH12_PH12") (pintype "bidirectional"))
    )
    (net (code "183") (name "unconnected-(U$2-PadPH13)") (class "Default")
      (node (ref "U$2") (pin "PH13") (pinfunction "PH13_PH13") (pintype "bidirectional"))
    )
    (net (code "184") (name "unconnected-(U$2-PadPH15)") (class "Default")
      (node (ref "U$2") (pin "PH15") (pinfunction "PH15_PH15") (pintype "bidirectional"))
    )
    (net (code "185") (name "unconnected-(U$2-PadPI0)") (class "Default")
      (node (ref "U$2") (pin "PI0") (pinfunction "PI0_PI0") (pintype "bidirectional"))
    )
    (net (code "186") (name "unconnected-(U$2-PadPI1)") (class "Default")
      (node (ref "U$2") (pin "PI1") (pinfunction "PI1_PI1") (pintype "bidirectional"))
    )
    (net (code "187") (name "unconnected-(U$2-PadPI3)") (class "Default")
      (node (ref "U$2") (pin "PI3") (pinfunction "PI3_PI3") (pintype "bidirectional"))
    )
    (net (code "188") (name "unconnected-(U$2-PadPI6)") (class "Default")
      (node (ref "U$2") (pin "PI6") (pinfunction "PI6_PI6") (pintype "bidirectional"))
    )
    (net (code "189") (name "unconnected-(U$2-PadPI7)") (class "Default")
      (node (ref "U$2") (pin "PI7") (pinfunction "PI7_PI7") (pintype "bidirectional"))
    )
    (net (code "190") (name "unconnected-(U$2-PadPI8)") (class "Default")
      (node (ref "U$2") (pin "PI8") (pinfunction "PI8_PI8") (pintype "bidirectional"))
    )
    (net (code "191") (name "unconnected-(U$2-PadPI11)") (class "Default")
      (node (ref "U$2") (pin "PI11") (pinfunction "PI11_PI11") (pintype "bidirectional"))
    )
    (net (code "192") (name "unconnected-(U$2-PadRST)") (class "Default")
      (node (ref "U$2") (pin "RST") (pinfunction "RST_RST") (pintype "bidirectional"))
    )
    (net (code "193") (name "unconnected-(U$2-PadVBAT)") (class "Default")
      (node (ref "U$2") (pin "VBAT") (pinfunction "VBAT_VBAT") (pintype "bidirectional"))
    )
    (net (code "194") (name "unconnected-(U$2-PadVREF+)") (class "Default")
      (node (ref "U$2") (pin "VREF+") (pinfunction "VREF+_VREF+") (pintype "bidirectional"))
    )
    (net (code "195") (name "unconnected-(U$3-P$1-PadTXD)") (class "Default")
      (node (ref "U$3") (pin "TXD") (pinfunction "P$1_TXD") (pintype "bidirectional"))
    )
    (net (code "196") (name "unconnected-(U$3-P$2-PadRXD)") (class "Default")
      (node (ref "U$3") (pin "RXD") (pinfunction "P$2_RXD") (pintype "bidirectional"))
    )
    (net (code "197") (name "unconnected-(U$3-P$3-PadGPIO4)") (class "Default")
      (node (ref "U$3") (pin "GPIO4") (pinfunction "P$3_GPIO4") (pintype "bidirectional"))
    )
    (net (code "198") (name "unconnected-(U$3-P$4-PadGPIO5)") (class "Default")
      (node (ref "U$3") (pin "GPIO5") (pinfunction "P$4_GPIO5") (pintype "bidirectional"))
    )
    (net (code "199") (name "unconnected-(U$3-P$6-PadGPIO2)") (class "Default")
      (node (ref "U$3") (pin "GPIO2") (pinfunction "P$6_GPIO2") (pintype "bidirectional"))
    )
    (net (code "200") (name "unconnected-(U$3-P$7-PadGPIO15)") (class "Default")
      (node (ref "U$3") (pin "GPIO15") (pinfunction "P$7_GPIO15") (pintype "bidirectional"))
    )
    (net (code "201") (name "unconnected-(U$3-P$10-PadGPIO13)") (class "Default")
      (node (ref "U$3") (pin "GPIO13") (pinfunction "P$10_GPIO13") (pintype "bidirectional"))
    )
    (net (code "202") (name "unconnected-(U$3-P$11-PadGPIO12)") (class "Default")
      (node (ref "U$3") (pin "GPIO12") (pinfunction "P$11_GPIO12") (pintype "bidirectional"))
    )
    (net (code "203") (name "unconnected-(U$3-P$12-PadGPIO14)") (class "Default")
      (node (ref "U$3") (pin "GPIO14") (pinfunction "P$12_GPIO14") (pintype "bidirectional"))
    )
    (net (code "204") (name "unconnected-(U$3-P$13-PadGPIO16)") (class "Default")
      (node (ref "U$3") (pin "GPIO16") (pinfunction "P$13_GPIO16") (pintype "bidirectional"))
    )
    (net (code "205") (name "unconnected-(U$3-P$15-PadADC)") (class "Default")
      (node (ref "U$3") (pin "ADC") (pinfunction "P$15_ADC") (pintype "bidirectional"))
    )
    (net (code "206") (name "unconnected-(U1-ADDR-Pad5)") (class "Default")
      (node (ref "U1") (pin "5") (pinfunction "ADDR_5") (pintype "bidirectional"))
    )
    (net (code "207") (name "unconnected-(U1-ALRT-Pad6)") (class "Default")
      (node (ref "U1") (pin "6") (pinfunction "ALRT_6") (pintype "bidirectional"))
    )
  )
)
